# XT_short_bus_with_break-away_tab.net
KiCad netlist of a schematic drawn in Altium Designer
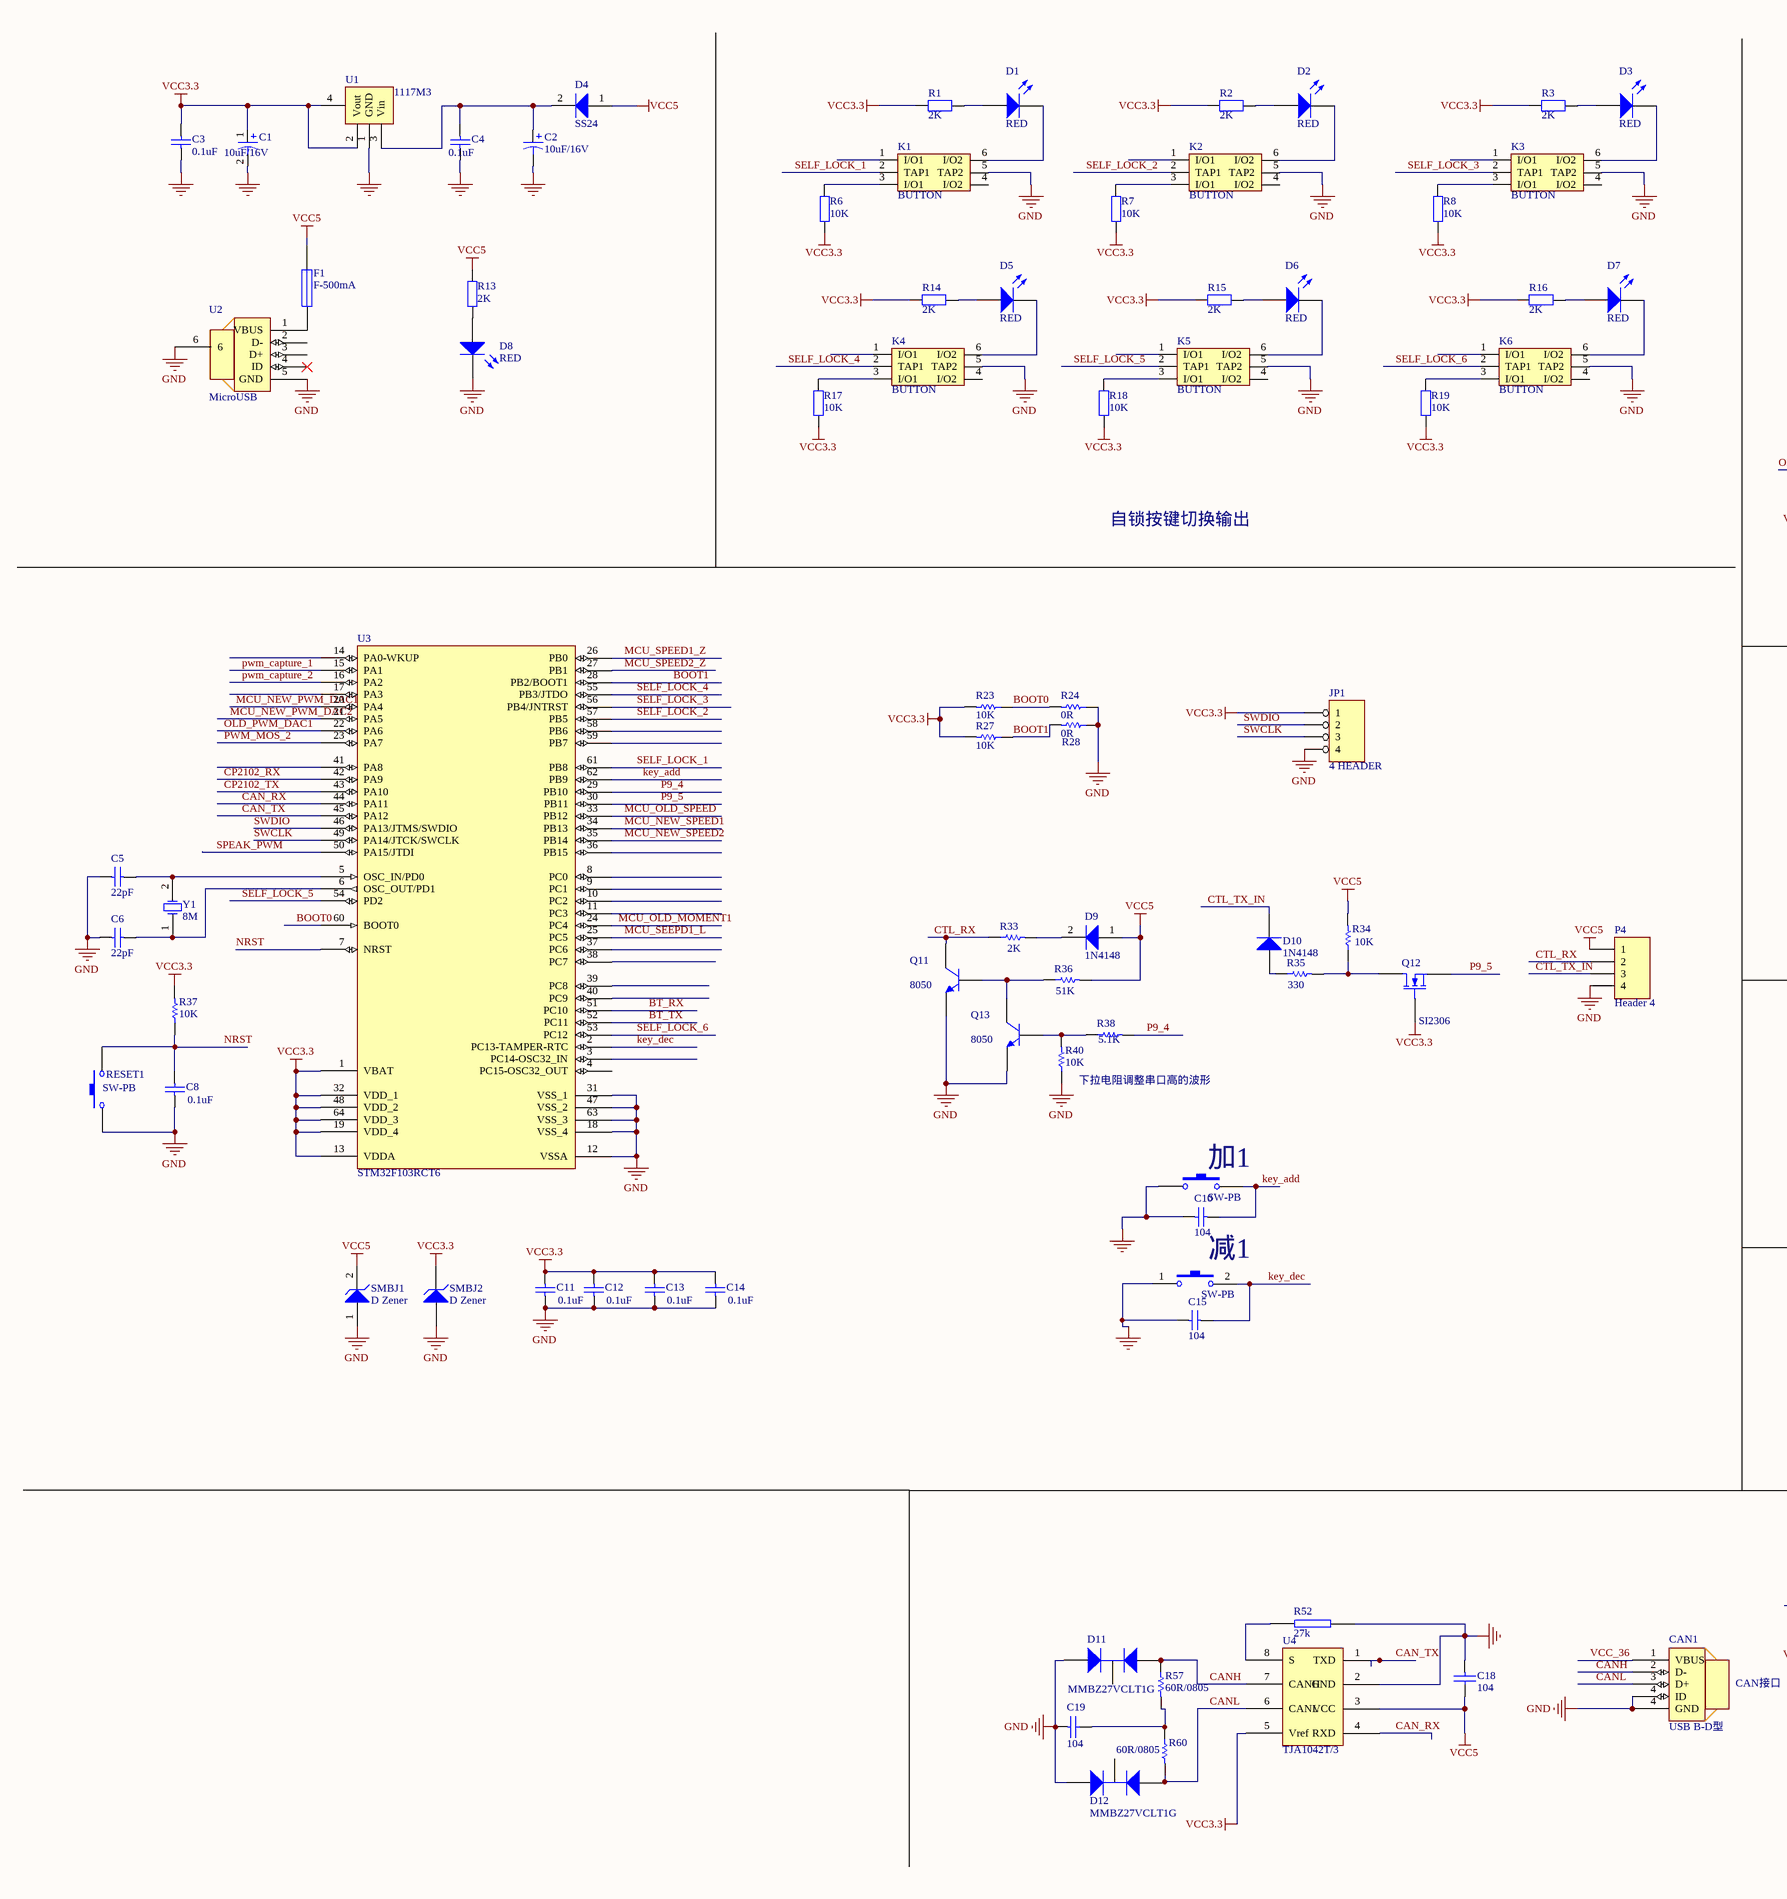
[diagram p0: XT short bus with break-away tab ( 5.2 X 4.2 inches).schdoc, left]
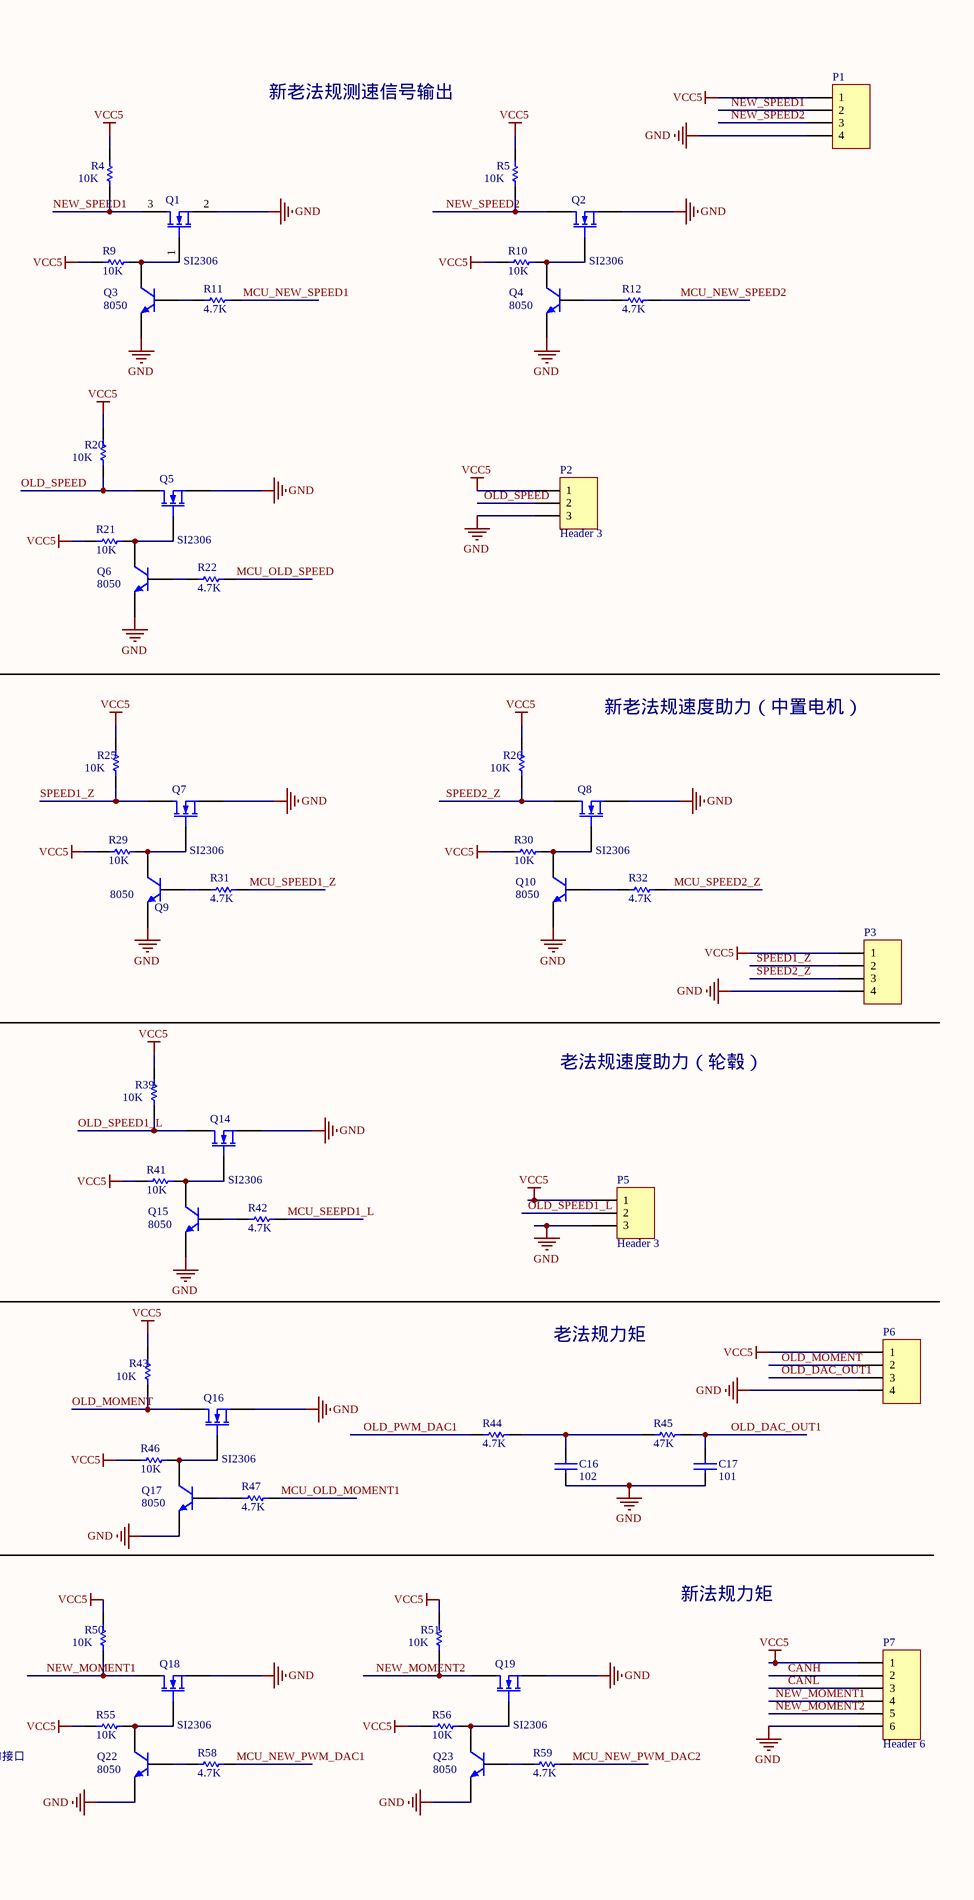
[diagram p1: XT short bus with break-away tab ( 5.2 X 4.2 inches).schdoc, right]

(export (version "E")
  (design (tool "Eeschema 10.0.6"))
  (components
    (comp (ref "C1")
      (value "10uF/16V")
      (footprint "1206")
      (description "Polarized Capacitor (Radial)")
      (fields (field (name "PUBLISHER") "Altium Limited"))
      (libsource (lib "") (part "Cap Pol1_1"))
    )
    (comp (ref "C2")
      (value "10uF/16V")
      (footprint "1206")
      (description "Polarized Capacitor (Radial)")
      (fields (field (name "PUBLISHER") "Altium Limited"))
      (libsource (lib "系统元件") (part "Cap Pol1"))
    )
    (comp (ref "C3")
      (value "0.1uF")
      (footprint "LC-0603_C")
      (description "Capacitor")
      (fields (field (name "PUBLISHER") "Altium Limited"))
      (libsource (lib "Miscellaneous Devices") (part "Cap"))
    )
    (comp (ref "C4")
      (value "0.1uF")
      (footprint "LC-0603_C")
      (description "Capacitor")
      (fields (field (name "PUBLISHER") "Altium Limited"))
      (libsource (lib "Miscellaneous Devices") (part "Cap"))
    )
    (comp (ref "C5")
      (value "22pF")
      (footprint "LC-0603_C")
      (description "Capacitor")
      (fields (field (name "PUBLISHER") "Altium Limited"))
      (libsource (lib "Miscellaneous Devices") (part "Cap"))
    )
    (comp (ref "C6")
      (value "22pF")
      (footprint "LC-0603_C")
      (description "Capacitor")
      (fields (field (name "PUBLISHER") "Altium Limited"))
      (libsource (lib "Miscellaneous Devices") (part "Cap"))
    )
    (comp (ref "C8")
      (value "0.1uF")
      (footprint "LC-0603_C")
      (description "Capacitor")
      (fields (field (name "PUBLISHER") "Altium Limited"))
      (libsource (lib "Miscellaneous Devices") (part "Cap"))
    )
    (comp (ref "C10")
      (value "104")
      (footprint "LC-0603_C")
      (description "Capacitor")
      (fields (field (name "PUBLISHER") "Altium Limited"))
      (libsource (lib "Miscellaneous Devices") (part "Cap"))
    )
    (comp (ref "C11")
      (value "0.1uF")
      (footprint "LC-0603_C")
      (description "Capacitor")
      (fields (field (name "PUBLISHER") "Altium Limited"))
      (libsource (lib "Miscellaneous Devices") (part "Cap"))
    )
    (comp (ref "C12")
      (value "0.1uF")
      (footprint "LC-0603_C")
      (description "Capacitor")
      (fields (field (name "PUBLISHER") "Altium Limited"))
      (libsource (lib "Miscellaneous Devices") (part "Cap"))
    )
    (comp (ref "C13")
      (value "0.1uF")
      (footprint "LC-0603_C")
      (description "Capacitor")
      (fields (field (name "PUBLISHER") "Altium Limited"))
      (libsource (lib "Miscellaneous Devices") (part "Cap"))
    )
    (comp (ref "C14")
      (value "0.1uF")
      (footprint "LC-0603_C")
      (description "Capacitor")
      (fields (field (name "PUBLISHER") "Altium Limited"))
      (libsource (lib "Miscellaneous Devices") (part "Cap"))
    )
    (comp (ref "C15")
      (value "104")
      (footprint "LC-0603_C")
      (description "Capacitor")
      (fields (field (name "PUBLISHER") "Altium Limited"))
      (libsource (lib "Miscellaneous Devices") (part "Cap"))
    )
    (comp (ref "C16")
      (value "102")
      (footprint "LC-0603_C")
      (description "Capacitor")
      (libsource (lib "*") (part "CAP"))
    )
    (comp (ref "C17")
      (value "101")
      (footprint "LC-0603_C")
      (description "Capacitor")
      (libsource (lib "*") (part "CAP"))
    )
    (comp (ref "C18")
      (value "104")
      (footprint "LC-0603_C")
      (description "Capacitor")
      (libsource (lib "*") (part "CAP"))
    )
    (comp (ref "C19")
      (value "104")
      (footprint "LC-0603_C")
      (description "Capacitor")
      (libsource (lib "*") (part "CAP"))
    )
    (comp (ref "CAN1")
      (value "USB B-D型")
      (footprint "USB B-D型_2")
      (description "MINIUSB")
      (libsource (lib "Hand_device") (part "MINIUSB"))
    )
    (comp (ref "D1")
      (value "RED")
      (footprint "LED_A2")
      (description "Typical INFRARED GaAs LED")
      (fields (field (name "PUBLISHER") "Altium Limited"))
      (libsource (lib "Miscellaneous Devices") (part "LED0"))
    )
    (comp (ref "D2")
      (value "RED")
      (footprint "LED_A2")
      (description "Typical INFRARED GaAs LED")
      (fields (field (name "PUBLISHER") "Altium Limited"))
      (libsource (lib "Miscellaneous Devices") (part "LED0"))
    )
    (comp (ref "D3")
      (value "RED")
      (footprint "LED_A2")
      (description "Typical INFRARED GaAs LED")
      (fields (field (name "PUBLISHER") "Altium Limited"))
      (libsource (lib "Miscellaneous Devices") (part "LED0"))
    )
    (comp (ref "D4")
      (value "SS24")
      (footprint "LC-SMA(DO-214AC)_S1")
      (description "1 Amp General Purpose Rectifier")
      (fields (field (name "PUBLISHER") "Altium Limited"))
      (libsource (lib "") (part "Diode 1N4007_1"))
    )
    (comp (ref "D5")
      (value "RED")
      (footprint "LED_A2")
      (description "Typical INFRARED GaAs LED")
      (fields (field (name "PUBLISHER") "Altium Limited"))
      (libsource (lib "Miscellaneous Devices") (part "LED0"))
    )
    (comp (ref "D6")
      (value "RED")
      (footprint "LED_A2")
      (description "Typical INFRARED GaAs LED")
      (fields (field (name "PUBLISHER") "Altium Limited"))
      (libsource (lib "Miscellaneous Devices") (part "LED0"))
    )
    (comp (ref "D7")
      (value "RED")
      (footprint "LED_A2")
      (description "Typical INFRARED GaAs LED")
      (fields (field (name "PUBLISHER") "Altium Limited"))
      (libsource (lib "Miscellaneous Devices") (part "LED0"))
    )
    (comp (ref "D8")
      (value "RED")
      (footprint "LED_A2")
      (description "Typical INFRARED GaAs LED")
      (fields (field (name "PUBLISHER") "Altium Limited"))
      (libsource (lib "Miscellaneous Devices") (part "LED0"))
    )
    (comp (ref "D9")
      (value "1N4148")
      (footprint "DIODE_SOP")
      (description "1 Amp General Purpose Rectifier")
      (fields (field (name "PUBLISHER") "Altium Limited"))
      (libsource (lib "") (part "Diode 1N4007_1"))
    )
    (comp (ref "D10")
      (value "1N4148")
      (footprint "DIODE_SOP")
      (description "1 Amp General Purpose Rectifier")
      (fields (field (name "PUBLISHER") "Altium Limited"))
      (libsource (lib "Miscellaneous Devices") (part "Diode 1N4007"))
    )
    (comp (ref "D11")
      (value "MMBZ27VCLT1G")
      (footprint "SOT-23")
      (description "TVS二极管,  MMBZ27VCLT1G, 27V, 两个共阴极, SOT-23")
      (libsource (lib "LEOPARD_SYSTEM") (part "BAT54C"))
    )
    (comp (ref "D12")
      (value "MMBZ27VCLT1G")
      (footprint "sot-23")
      (description "TVS二极管,  MMBZ27VCLT1G, 27V, 两个共阴极, SOT-23")
      (libsource (lib "LEOPARD_SYSTEM") (part "BAT54C"))
    )
    (comp (ref "F1")
      (value "F-500mA")
      (footprint "1206A")
      (description "FUSE1")
      (libsource (lib "Hand_device") (part "FUSE1"))
    )
    (comp (ref "JP1")
      (value "4 HEADER")
      (footprint "HDR1X4")
      (description "4 Pin Header")
      (libsource (lib "杂元件库") (part "4 HEADER"))
    )
    (comp (ref "K1")
      (value "BUTTON")
      (footprint "BTN8.5*8.5")
      (libsource (lib "MiniSTM32 V3.0封装库") (part "BUTTON"))
    )
    (comp (ref "K2")
      (value "BUTTON")
      (footprint "BTN8.5*8.5")
      (libsource (lib "MiniSTM32 V3.0封装库") (part "BUTTON"))
    )
    (comp (ref "K3")
      (value "BUTTON")
      (footprint "BTN8.5*8.5")
      (libsource (lib "MiniSTM32 V3.0封装库") (part "BUTTON"))
    )
    (comp (ref "K4")
      (value "BUTTON")
      (footprint "BTN8.5*8.5")
      (libsource (lib "MiniSTM32 V3.0封装库") (part "BUTTON"))
    )
    (comp (ref "K5")
      (value "BUTTON")
      (footprint "BTN8.5*8.5")
      (libsource (lib "MiniSTM32 V3.0封装库") (part "BUTTON"))
    )
    (comp (ref "K6")
      (value "BUTTON")
      (footprint "BTN8.5*8.5")
      (libsource (lib "MiniSTM32 V3.0封装库") (part "BUTTON"))
    )
    (comp (ref "P1")
      (value "Header 4")
      (footprint "HDR1X4")
      (description "Header, 4-Pin")
      (fields (field (name "PUBLISHER") "Altium Limited"))
      (libsource (lib "Miscellaneous Connectors") (part "Header 4"))
    )
    (comp (ref "P2")
      (value "Header 3")
      (footprint "HDR1X3")
      (description "Header, 3-Pin")
      (fields (field (name "PUBLISHER") "Altium Limited"))
      (libsource (lib "Miscellaneous Connectors") (part "Header 3"))
    )
    (comp (ref "P3")
      (value "Header 4")
      (footprint "HDR1X4")
      (description "Header, 4-Pin")
      (fields (field (name "PUBLISHER") "Altium Limited"))
      (libsource (lib "Miscellaneous Connectors") (part "Header 4"))
    )
    (comp (ref "P4")
      (value "Header 4")
      (footprint "HDR1X4")
      (description "Header, 4-Pin")
      (fields (field (name "PUBLISHER") "Altium Limited"))
      (libsource (lib "Miscellaneous Connectors") (part "Header 4"))
    )
    (comp (ref "P5")
      (value "Header 3")
      (footprint "HDR1X3")
      (description "Header, 3-Pin")
      (fields (field (name "PUBLISHER") "Altium Limited"))
      (libsource (lib "Miscellaneous Connectors") (part "Header 3"))
    )
    (comp (ref "P6")
      (value "Header 4")
      (footprint "HDR1X4")
      (description "Header, 4-Pin")
      (fields (field (name "PUBLISHER") "Altium Limited"))
      (libsource (lib "Miscellaneous Connectors") (part "Header 4"))
    )
    (comp (ref "P7")
      (value "Header 6")
      (footprint "HDR1X6")
      (description "Header, 6-Pin")
      (fields (field (name "PUBLISHER") "Altium Limited"))
      (libsource (lib "Miscellaneous Connectors") (part "Header 6"))
    )
    (comp (ref "Q1")
      (value "SI2306")
      (footprint "sot-23")
      (description "N-Channel MOSFET")
      (fields (field (name "PUBLISHER") "Altium Limited"))
      (libsource (lib "") (part "MOSFET-N_1"))
    )
    (comp (ref "Q2")
      (value "SI2306")
      (footprint "sot-23")
      (description "N-Channel MOSFET")
      (fields (field (name "PUBLISHER") "Altium Limited"))
      (libsource (lib "系统元件") (part "MOSFET-N"))
    )
    (comp (ref "Q3")
      (value "8050")
      (footprint "sot-23")
      (description "NPN General Purpose Amplifier")
      (fields (field (name "PUBLISHER") "Altium Limited"))
      (libsource (lib "系统元件") (part "2N3904"))
    )
    (comp (ref "Q4")
      (value "8050")
      (footprint "sot-23")
      (description "NPN General Purpose Amplifier")
      (fields (field (name "PUBLISHER") "Altium Limited"))
      (libsource (lib "系统元件") (part "2N3904"))
    )
    (comp (ref "Q5")
      (value "SI2306")
      (footprint "sot-23")
      (description "N-Channel MOSFET")
      (fields (field (name "PUBLISHER") "Altium Limited"))
      (libsource (lib "系统元件") (part "MOSFET-N"))
    )
    (comp (ref "Q6")
      (value "8050")
      (footprint "sot-23")
      (description "NPN General Purpose Amplifier")
      (fields (field (name "PUBLISHER") "Altium Limited"))
      (libsource (lib "系统元件") (part "2N3904"))
    )
    (comp (ref "Q7")
      (value "SI2306")
      (footprint "sot-23")
      (description "N-Channel MOSFET")
      (fields (field (name "PUBLISHER") "Altium Limited"))
      (libsource (lib "系统元件") (part "MOSFET-N"))
    )
    (comp (ref "Q8")
      (value "SI2306")
      (footprint "sot-23")
      (description "N-Channel MOSFET")
      (fields (field (name "PUBLISHER") "Altium Limited"))
      (libsource (lib "系统元件") (part "MOSFET-N"))
    )
    (comp (ref "Q9")
      (value "8050")
      (footprint "sot-23")
      (description "NPN General Purpose Amplifier")
      (fields (field (name "PUBLISHER") "Altium Limited"))
      (libsource (lib "系统元件") (part "2N3904"))
    )
    (comp (ref "Q10")
      (value "8050")
      (footprint "sot-23")
      (description "NPN General Purpose Amplifier")
      (fields (field (name "PUBLISHER") "Altium Limited"))
      (libsource (lib "系统元件") (part "2N3904"))
    )
    (comp (ref "Q11")
      (value "8050")
      (footprint "sot-23")
      (description "NPN General Purpose Amplifier")
      (fields (field (name "PUBLISHER") "Altium Limited"))
      (libsource (lib "系统元件") (part "2N3904"))
    )
    (comp (ref "Q12")
      (value "SI2306")
      (footprint "sot-23")
      (description "N-Channel MOSFET")
      (fields (field (name "PUBLISHER") "Altium Limited"))
      (libsource (lib "系统元件") (part "MOSFET-N"))
    )
    (comp (ref "Q13")
      (value "8050")
      (footprint "sot-23")
      (description "NPN General Purpose Amplifier")
      (fields (field (name "PUBLISHER") "Altium Limited"))
      (libsource (lib "系统元件") (part "2N3904"))
    )
    (comp (ref "Q14")
      (value "SI2306")
      (footprint "sot-23")
      (description "N-Channel MOSFET")
      (fields (field (name "PUBLISHER") "Altium Limited"))
      (libsource (lib "系统元件") (part "MOSFET-N"))
    )
    (comp (ref "Q15")
      (value "8050")
      (footprint "sot-23")
      (description "NPN General Purpose Amplifier")
      (fields (field (name "PUBLISHER") "Altium Limited"))
      (libsource (lib "系统元件") (part "2N3904"))
    )
    (comp (ref "Q16")
      (value "SI2306")
      (footprint "sot-23")
      (description "N-Channel MOSFET")
      (fields (field (name "PUBLISHER") "Altium Limited"))
      (libsource (lib "系统元件") (part "MOSFET-N"))
    )
    (comp (ref "Q17")
      (value "8050")
      (footprint "sot-23")
      (description "NPN General Purpose Amplifier")
      (fields (field (name "PUBLISHER") "Altium Limited"))
      (libsource (lib "系统元件") (part "2N3904"))
    )
    (comp (ref "Q18")
      (value "SI2306")
      (footprint "sot-23")
      (description "N-Channel MOSFET")
      (fields (field (name "PUBLISHER") "Altium Limited"))
      (libsource (lib "系统元件") (part "MOSFET-N"))
    )
    (comp (ref "Q19")
      (value "SI2306")
      (footprint "sot-23")
      (description "N-Channel MOSFET")
      (fields (field (name "PUBLISHER") "Altium Limited"))
      (libsource (lib "系统元件") (part "MOSFET-N"))
    )
    (comp (ref "Q22")
      (value "8050")
      (footprint "sot-23")
      (description "NPN General Purpose Amplifier")
      (fields (field (name "PUBLISHER") "Altium Limited"))
      (libsource (lib "系统元件") (part "2N3904"))
    )
    (comp (ref "Q23")
      (value "8050")
      (footprint "sot-23")
      (description "NPN General Purpose Amplifier")
      (fields (field (name "PUBLISHER") "Altium Limited"))
      (libsource (lib "系统元件") (part "2N3904"))
    )
    (comp (ref "R1")
      (value "2K")
      (footprint "LC-0603_R")
      (description "Resistor")
      (fields (field (name "PUBLISHER") "Altium Limited"))
      (libsource (lib "") (part "Res2_1"))
    )
    (comp (ref "R2")
      (value "2K")
      (footprint "LC-0603_R")
      (description "Resistor")
      (fields (field (name "PUBLISHER") "Altium Limited"))
      (libsource (lib "") (part "Res2_1"))
    )
    (comp (ref "R3")
      (value "2K")
      (footprint "LC-0603_R")
      (description "Resistor")
      (fields (field (name "PUBLISHER") "Altium Limited"))
      (libsource (lib "") (part "Res2_1"))
    )
    (comp (ref "R4")
      (value "10K")
      (footprint "LC-0603_R")
      (description "Resistor")
      (fields (field (name "PUBLISHER") "Altium Limited"))
      (libsource (lib "Miscellaneous Devices") (part "Res1"))
    )
    (comp (ref "R5")
      (value "10K")
      (footprint "LC-0603_R")
      (description "Resistor")
      (fields (field (name "PUBLISHER") "Altium Limited"))
      (libsource (lib "Miscellaneous Devices") (part "Res1"))
    )
    (comp (ref "R6")
      (value "10K")
      (footprint "LC-0603_R")
      (description "Resistor")
      (fields (field (name "PUBLISHER") "Altium Limited"))
      (libsource (lib "Miscellaneous Devices") (part "Res2"))
    )
    (comp (ref "R7")
      (value "10K")
      (footprint "LC-0603_R")
      (description "Resistor")
      (fields (field (name "PUBLISHER") "Altium Limited"))
      (libsource (lib "Miscellaneous Devices") (part "Res2"))
    )
    (comp (ref "R8")
      (value "10K")
      (footprint "LC-0603_R")
      (description "Resistor")
      (fields (field (name "PUBLISHER") "Altium Limited"))
      (libsource (lib "Miscellaneous Devices") (part "Res2"))
    )
    (comp (ref "R9")
      (value "10K")
      (footprint "LC-0603_R")
      (description "Resistor")
      (fields (field (name "PUBLISHER") "Altium Limited"))
      (libsource (lib "Miscellaneous Devices") (part "Res1"))
    )
    (comp (ref "R10")
      (value "10K")
      (footprint "LC-0603_R")
      (description "Resistor")
      (fields (field (name "PUBLISHER") "Altium Limited"))
      (libsource (lib "Miscellaneous Devices") (part "Res1"))
    )
    (comp (ref "R11")
      (value "4.7K")
      (footprint "LC-0603_R")
      (description "Resistor")
      (fields (field (name "PUBLISHER") "Altium Limited"))
      (libsource (lib "Miscellaneous Devices") (part "Res1"))
    )
    (comp (ref "R12")
      (value "4.7K")
      (footprint "LC-0603_R")
      (description "Resistor")
      (fields (field (name "PUBLISHER") "Altium Limited"))
      (libsource (lib "Miscellaneous Devices") (part "Res1"))
    )
    (comp (ref "R13")
      (value "2K")
      (footprint "LC-0603_R")
      (description "Resistor")
      (fields (field (name "PUBLISHER") "Altium Limited"))
      (libsource (lib "Miscellaneous Devices") (part "Res2"))
    )
    (comp (ref "R14")
      (value "2K")
      (footprint "LC-0603_R")
      (description "Resistor")
      (fields (field (name "PUBLISHER") "Altium Limited"))
      (libsource (lib "") (part "Res2_1"))
    )
    (comp (ref "R15")
      (value "2K")
      (footprint "LC-0603_R")
      (description "Resistor")
      (fields (field (name "PUBLISHER") "Altium Limited"))
      (libsource (lib "") (part "Res2_1"))
    )
    (comp (ref "R16")
      (value "2K")
      (footprint "LC-0603_R")
      (description "Resistor")
      (fields (field (name "PUBLISHER") "Altium Limited"))
      (libsource (lib "") (part "Res2_1"))
    )
    (comp (ref "R17")
      (value "10K")
      (footprint "LC-0603_R")
      (description "Resistor")
      (fields (field (name "PUBLISHER") "Altium Limited"))
      (libsource (lib "Miscellaneous Devices") (part "Res2"))
    )
    (comp (ref "R18")
      (value "10K")
      (footprint "LC-0603_R")
      (description "Resistor")
      (fields (field (name "PUBLISHER") "Altium Limited"))
      (libsource (lib "Miscellaneous Devices") (part "Res2"))
    )
    (comp (ref "R19")
      (value "10K")
      (footprint "LC-0603_R")
      (description "Resistor")
      (fields (field (name "PUBLISHER") "Altium Limited"))
      (libsource (lib "Miscellaneous Devices") (part "Res2"))
    )
    (comp (ref "R20")
      (value "10K")
      (footprint "LC-0603_R")
      (description "Resistor")
      (fields (field (name "PUBLISHER") "Altium Limited"))
      (libsource (lib "Miscellaneous Devices") (part "Res1"))
    )
    (comp (ref "R21")
      (value "10K")
      (footprint "LC-0603_R")
      (description "Resistor")
      (fields (field (name "PUBLISHER") "Altium Limited"))
      (libsource (lib "Miscellaneous Devices") (part "Res1"))
    )
    (comp (ref "R22")
      (value "4.7K")
      (footprint "LC-0603_R")
      (description "Resistor")
      (fields (field (name "PUBLISHER") "Altium Limited"))
      (libsource (lib "Miscellaneous Devices") (part "Res1"))
    )
    (comp (ref "R23")
      (value "10K")
      (footprint "LC-0603_R")
      (description "Resistor")
      (fields (field (name "PUBLISHER") "Altium Limited"))
      (libsource (lib "Miscellaneous Devices") (part "Res1"))
    )
    (comp (ref "R24")
      (value "0R")
      (footprint "LC-0603_R")
      (description "Resistor")
      (fields (field (name "PUBLISHER") "Altium Limited"))
      (libsource (lib "Miscellaneous Devices") (part "Res1"))
    )
    (comp (ref "R25")
      (value "10K")
      (footprint "LC-0603_R")
      (description "Resistor")
      (fields (field (name "PUBLISHER") "Altium Limited"))
      (libsource (lib "Miscellaneous Devices") (part "Res1"))
    )
    (comp (ref "R26")
      (value "10K")
      (footprint "LC-0603_R")
      (description "Resistor")
      (fields (field (name "PUBLISHER") "Altium Limited"))
      (libsource (lib "Miscellaneous Devices") (part "Res1"))
    )
    (comp (ref "R27")
      (value "10K")
      (footprint "LC-0603_R")
      (description "Resistor")
      (fields (field (name "PUBLISHER") "Altium Limited"))
      (libsource (lib "Miscellaneous Devices") (part "Res1"))
    )
    (comp (ref "R28")
      (value "0R")
      (footprint "LC-0603_R")
      (description "Resistor")
      (fields (field (name "PUBLISHER") "Altium Limited"))
      (libsource (lib "Miscellaneous Devices") (part "Res1"))
    )
    (comp (ref "R29")
      (value "10K")
      (footprint "LC-0603_R")
      (description "Resistor")
      (fields (field (name "PUBLISHER") "Altium Limited"))
      (libsource (lib "Miscellaneous Devices") (part "Res1"))
    )
    (comp (ref "R30")
      (value "10K")
      (footprint "LC-0603_R")
      (description "Resistor")
      (fields (field (name "PUBLISHER") "Altium Limited"))
      (libsource (lib "Miscellaneous Devices") (part "Res1"))
    )
    (comp (ref "R31")
      (value "4.7K")
      (footprint "LC-0603_R")
      (description "Resistor")
      (fields (field (name "PUBLISHER") "Altium Limited"))
      (libsource (lib "Miscellaneous Devices") (part "Res1"))
    )
    (comp (ref "R32")
      (value "4.7K")
      (footprint "LC-0603_R")
      (description "Resistor")
      (fields (field (name "PUBLISHER") "Altium Limited"))
      (libsource (lib "Miscellaneous Devices") (part "Res1"))
    )
    (comp (ref "R33")
      (value "2K")
      (footprint "LC-0603_R")
      (description "Resistor")
      (fields (field (name "PUBLISHER") "Altium Limited"))
      (libsource (lib "Miscellaneous Devices") (part "Res1"))
    )
    (comp (ref "R34")
      (value "10K")
      (footprint "LC-0603_R")
      (description "Resistor")
      (fields (field (name "PUBLISHER") "Altium Limited"))
      (libsource (lib "Miscellaneous Devices") (part "Res1"))
    )
    (comp (ref "R35")
      (value "330")
      (footprint "LC-0603_R")
      (description "Resistor")
      (fields (field (name "PUBLISHER") "Altium Limited"))
      (libsource (lib "Miscellaneous Devices") (part "Res1"))
    )
    (comp (ref "R36")
      (value "51K")
      (footprint "LC-0603_R")
      (description "Resistor")
      (fields (field (name "PUBLISHER") "Altium Limited"))
      (libsource (lib "Miscellaneous Devices") (part "Res1"))
    )
    (comp (ref "R37")
      (value "10K")
      (footprint "LC-0603_R")
      (description "Resistor")
      (fields (field (name "PUBLISHER") "Altium Limited"))
      (libsource (lib "Miscellaneous Devices") (part "Res1"))
    )
    (comp (ref "R38")
      (value "5.1K")
      (footprint "LC-0603_R")
      (description "Resistor")
      (fields (field (name "PUBLISHER") "Altium Limited"))
      (libsource (lib "Miscellaneous Devices") (part "Res1"))
    )
    (comp (ref "R39")
      (value "10K")
      (footprint "LC-0603_R")
      (description "Resistor")
      (fields (field (name "PUBLISHER") "Altium Limited"))
      (libsource (lib "Miscellaneous Devices") (part "Res1"))
    )
    (comp (ref "R40")
      (value "10K")
      (footprint "LC-0603_R")
      (description "Resistor")
      (fields (field (name "PUBLISHER") "Altium Limited"))
      (libsource (lib "Miscellaneous Devices") (part "Res1"))
    )
    (comp (ref "R41")
      (value "10K")
      (footprint "LC-0603_R")
      (description "Resistor")
      (fields (field (name "PUBLISHER") "Altium Limited"))
      (libsource (lib "Miscellaneous Devices") (part "Res1"))
    )
    (comp (ref "R42")
      (value "4.7K")
      (footprint "LC-0603_R")
      (description "Resistor")
      (fields (field (name "PUBLISHER") "Altium Limited"))
      (libsource (lib "Miscellaneous Devices") (part "Res1"))
    )
    (comp (ref "R43")
      (value "10K")
      (footprint "LC-0603_R")
      (description "Resistor")
      (fields (field (name "PUBLISHER") "Altium Limited"))
      (libsource (lib "Miscellaneous Devices") (part "Res1"))
    )
    (comp (ref "R44")
      (value "4.7K")
      (footprint "LC-0603_R")
      (description "Resistor")
      (fields (field (name "PUBLISHER") "Altium Limited"))
      (libsource (lib "Miscellaneous Devices") (part "Res1"))
    )
    (comp (ref "R45")
      (value "47K")
      (footprint "LC-0603_R")
      (description "Resistor")
      (fields (field (name "PUBLISHER") "Altium Limited"))
      (libsource (lib "Miscellaneous Devices") (part "Res1"))
    )
    (comp (ref "R46")
      (value "10K")
      (footprint "LC-0603_R")
      (description "Resistor")
      (fields (field (name "PUBLISHER") "Altium Limited"))
      (libsource (lib "Miscellaneous Devices") (part "Res1"))
    )
    (comp (ref "R47")
      (value "4.7K")
      (footprint "LC-0603_R")
      (description "Resistor")
      (fields (field (name "PUBLISHER") "Altium Limited"))
      (libsource (lib "Miscellaneous Devices") (part "Res1"))
    )
    (comp (ref "R50")
      (value "10K")
      (footprint "LC-0603_R")
      (description "Resistor")
      (fields (field (name "PUBLISHER") "Altium Limited"))
      (libsource (lib "Miscellaneous Devices") (part "Res1"))
    )
    (comp (ref "R51")
      (value "10K")
      (footprint "LC-0603_R")
      (description "Resistor")
      (fields (field (name "PUBLISHER") "Altium Limited"))
      (libsource (lib "Miscellaneous Devices") (part "Res1"))
    )
    (comp (ref "R52") (value "27k") (footprint "LC-0603_R") (libsource (lib "*") (part "RES2")))
    (comp (ref "R55")
      (value "10K")
      (footprint "LC-0603_R")
      (description "Resistor")
      (fields (field (name "PUBLISHER") "Altium Limited"))
      (libsource (lib "Miscellaneous Devices") (part "Res1"))
    )
    (comp (ref "R56")
      (value "10K")
      (footprint "LC-0603_R")
      (description "Resistor")
      (fields (field (name "PUBLISHER") "Altium Limited"))
      (libsource (lib "Miscellaneous Devices") (part "Res1"))
    )
    (comp (ref "R57")
      (value "60R/0805")
      (footprint "LC-0603_R")
      (description "Resistor")
      (fields (field (name "PUBLISHER") "Altium Limited"))
      (libsource (lib "Miscellaneous Devices") (part "Res1"))
    )
    (comp (ref "R58")
      (value "4.7K")
      (footprint "LC-0603_R")
      (description "Resistor")
      (fields (field (name "PUBLISHER") "Altium Limited"))
      (libsource (lib "Miscellaneous Devices") (part "Res1"))
    )
    (comp (ref "R59")
      (value "4.7K")
      (footprint "LC-0603_R")
      (description "Resistor")
      (fields (field (name "PUBLISHER") "Altium Limited"))
      (libsource (lib "Miscellaneous Devices") (part "Res1"))
    )
    (comp (ref "R60")
      (value "60R/0805")
      (footprint "LC-0603_R")
      (description "Resistor")
      (fields (field (name "PUBLISHER") "Altium Limited"))
      (libsource (lib "Miscellaneous Devices") (part "Res1"))
    )
    (comp (ref "RESET1")
      (value "SW-PB")
      (footprint "按键-贴片-6X6")
      (description "Switch")
      (fields (field (name "PUBLISHER") "Altium Limited"))
      (libsource (lib "Miscellaneous Devices") (part "SW-PB"))
    )
    (comp (ref "SMBJ1")
      (value "D Zener")
      (footprint "LC-SMB(DO-214AA)_S1")
      (description "Zener Diode")
      (fields (field (name "PUBLISHER") "Altium Limited"))
      (libsource (lib "") (part "D Zener_1"))
    )
    (comp (ref "SMBJ2")
      (value "D Zener")
      (footprint "LC-SMB(DO-214AA)_S1")
      (description "Zener Diode")
      (fields (field (name "PUBLISHER") "Altium Limited"))
      (libsource (lib "Miscellaneous Devices") (part "D Zener"))
    )
    (comp (ref "U1") (value "1117M3") (footprint "SOT-223") (libsource (lib "Schlib") (part "1117M3")))
    (comp (ref "U2")
      (value "MicroUSB")
      (footprint "USB1_mini_直插")
      (description "MINIUSB")
      (libsource (lib "") (part "MINIUSB_1"))
    )
    (comp (ref "U3")
      (value "STM32F103RCT6")
      (footprint "LC-LQFP-64_10X10X05P")
      (description "STM32 ARM-based 32-bit MCU with 128 Kbytes Flash, 64-pin LQFP, Industrial Temperature")
      (fields (field (name "PUBLISHER") "Altium Limited"))
      (libsource (lib "ST Microcontroller 32-Bit STM32") (part "STM32F103RBT6"))
    )
    (comp (ref "U4")
      (value "TJA1042T/3")
      (footprint "LC-SOP-8_150mil")
      (libsource (lib "*") (part "TJA1050"))
    )
    (comp (ref "Y1")
      (value "8M")
      (footprint "XTAL_US")
      (description "Crystal Oscillator")
      (fields (field (name "PUBLISHER") "Altium Limited"))
      (libsource (lib "Miscellaneous Devices") (part "XTAL"))
    )
    (comp (ref "减1")
      (value "SW-PB")
      (footprint "按键-贴片-6X6")
      (description "Switch")
      (fields (field (name "PUBLISHER") "Altium Limited"))
      (libsource (lib "") (part "SW-PB_1"))
    )
    (comp (ref "加1")
      (value "SW-PB")
      (footprint "按键-贴片-6X6")
      (description "Switch")
      (fields (field (name "PUBLISHER") "Altium Limited"))
      (libsource (lib "Miscellaneous Devices") (part "SW-PB"))
    )
  )
  (nets
    (net (code "1") (name "/BOOT0") (class "Default")
      (node (ref "R23") (pin "1") (pinfunction "1_1") (pintype "passive"))
      (node (ref "R24") (pin "2") (pinfunction "2_2") (pintype "passive"))
      (node (ref "U3") (pin "60") (pinfunction "BOOT0_60") (pintype "input"))
    )
    (net (code "2") (name "/BOOT1") (class "Default")
      (node (ref "R27") (pin "1") (pinfunction "1_1") (pintype "passive"))
      (node (ref "R28") (pin "2") (pinfunction "2_2") (pintype "passive"))
      (node (ref "U3") (pin "28") (pinfunction "PB2/BOOT1_28") (pintype "bidirectional"))
    )
    (net (code "3") (name "/BT_RX") (class "Default")
      (node (ref "U3") (pin "51") (pinfunction "PC10_51") (pintype "bidirectional"))
    )
    (net (code "4") (name "/BT_TX") (class "Default")
      (node (ref "U3") (pin "52") (pinfunction "PC11_52") (pintype "bidirectional"))
    )
    (net (code "5") (name "/CANH") (class "Default")
      (node (ref "CAN1") (pin "2") (pinfunction "D-_2") (pintype "bidirectional"))
      (node (ref "D11") (pin "2") (pinfunction "C_2") (pintype "passive"))
      (node (ref "P7") (pin "2") (pinfunction "2_2") (pintype "passive"))
      (node (ref "R57") (pin "1") (pinfunction "1_1") (pintype "passive"))
      (node (ref "U4") (pin "7") (pinfunction "CANH_7") (pintype "passive"))
    )
    (net (code "6") (name "/CANL") (class "Default")
      (node (ref "CAN1") (pin "3") (pinfunction "D+_3") (pintype "bidirectional"))
      (node (ref "D12") (pin "1") (pinfunction "A_1") (pintype "passive"))
      (node (ref "P7") (pin "3") (pinfunction "3_3") (pintype "passive"))
      (node (ref "R60") (pin "2") (pinfunction "2_2") (pintype "passive"))
      (node (ref "U4") (pin "6") (pinfunction "CANL_6") (pintype "passive"))
    )
    (net (code "7") (name "/CAN_RX") (class "Default")
      (node (ref "U3") (pin "44") (pinfunction "PA11_44") (pintype "bidirectional"))
      (node (ref "U4") (pin "4") (pinfunction "RXD_4") (pintype "passive"))
    )
    (net (code "8") (name "/CAN_TX") (class "Default")
      (node (ref "U3") (pin "45") (pinfunction "PA12_45") (pintype "bidirectional"))
      (node (ref "U4") (pin "1") (pinfunction "TXD_1") (pintype "passive"))
    )
    (net (code "9") (name "/CP2102_RX") (class "Default")
      (node (ref "U3") (pin "42") (pinfunction "PA9_42") (pintype "bidirectional"))
    )
    (net (code "10") (name "/CP2102_TX") (class "Default")
      (node (ref "U3") (pin "43") (pinfunction "PA10_43") (pintype "bidirectional"))
    )
    (net (code "11") (name "/CTL_RX") (class "Default")
      (node (ref "P4") (pin "2") (pinfunction "2_2") (pintype "passive"))
      (node (ref "Q11") (pin "3") (pinfunction "C_3") (pintype "passive"))
      (node (ref "R33") (pin "1") (pinfunction "1_1") (pintype "passive"))
    )
    (net (code "12") (name "/CTL_TX_IN") (class "Default")
      (node (ref "D10") (pin "2") (pinfunction "K_2") (pintype "passive"))
      (node (ref "P4") (pin "3") (pinfunction "3_3") (pintype "passive"))
    )
    (net (code "13") (name "/MCU_NEW_PWM_DAC1") (class "Default")
      (node (ref "R58") (pin "1") (pinfunction "1_1") (pintype "passive"))
      (node (ref "U3") (pin "20") (pinfunction "PA4_20") (pintype "bidirectional"))
    )
    (net (code "14") (name "/MCU_NEW_PWM_DAC2") (class "Default")
      (node (ref "R59") (pin "1") (pinfunction "1_1") (pintype "passive"))
      (node (ref "U3") (pin "21") (pinfunction "PA5_21") (pintype "bidirectional"))
    )
    (net (code "15") (name "/MCU_NEW_SPEED1") (class "Default")
      (node (ref "R11") (pin "1") (pinfunction "1_1") (pintype "passive"))
      (node (ref "U3") (pin "34") (pinfunction "PB13_34") (pintype "bidirectional"))
    )
    (net (code "16") (name "/MCU_NEW_SPEED2") (class "Default")
      (node (ref "R12") (pin "1") (pinfunction "1_1") (pintype "passive"))
      (node (ref "U3") (pin "35") (pinfunction "PB14_35") (pintype "bidirectional"))
    )
    (net (code "17") (name "/MCU_OLD_MOMENT1") (class "Default")
      (node (ref "R47") (pin "1") (pinfunction "1_1") (pintype "passive"))
      (node (ref "U3") (pin "24") (pinfunction "PC4_24") (pintype "bidirectional"))
    )
    (net (code "18") (name "/MCU_OLD_SPEED") (class "Default")
      (node (ref "R22") (pin "1") (pinfunction "1_1") (pintype "passive"))
      (node (ref "U3") (pin "33") (pinfunction "PB12_33") (pintype "bidirectional"))
    )
    (net (code "19") (name "/MCU_SEEPD1_L") (class "Default")
      (node (ref "R42") (pin "1") (pinfunction "1_1") (pintype "passive"))
      (node (ref "U3") (pin "25") (pinfunction "PC5_25") (pintype "bidirectional"))
    )
    (net (code "20") (name "/MCU_SPEED1_Z") (class "Default")
      (node (ref "R31") (pin "1") (pinfunction "1_1") (pintype "passive"))
      (node (ref "U3") (pin "26") (pinfunction "PB0_26") (pintype "bidirectional"))
    )
    (net (code "21") (name "/MCU_SPEED2_Z") (class "Default")
      (node (ref "R32") (pin "1") (pinfunction "1_1") (pintype "passive"))
      (node (ref "U3") (pin "27") (pinfunction "PB1_27") (pintype "bidirectional"))
    )
    (net (code "22") (name "/NEW_MOMENT1") (class "Default")
      (node (ref "P7") (pin "4") (pinfunction "4_4") (pintype "passive"))
      (node (ref "Q18") (pin "3") (pinfunction "D_3") (pintype "passive"))
      (node (ref "R50") (pin "1") (pinfunction "1_1") (pintype "passive"))
    )
    (net (code "23") (name "/NEW_MOMENT2") (class "Default")
      (node (ref "P7") (pin "5") (pinfunction "5_5") (pintype "passive"))
      (node (ref "Q19") (pin "3") (pinfunction "D_3") (pintype "passive"))
      (node (ref "R51") (pin "1") (pinfunction "1_1") (pintype "passive"))
    )
    (net (code "24") (name "/NEW_SPEED1") (class "Default")
      (node (ref "P1") (pin "2") (pinfunction "2_2") (pintype "passive"))
      (node (ref "Q1") (pin "3") (pinfunction "D_3") (pintype "passive"))
      (node (ref "R4") (pin "1") (pinfunction "1_1") (pintype "passive"))
    )
    (net (code "25") (name "/NEW_SPEED2") (class "Default")
      (node (ref "P1") (pin "3") (pinfunction "3_3") (pintype "passive"))
      (node (ref "Q2") (pin "3") (pinfunction "D_3") (pintype "passive"))
      (node (ref "R5") (pin "1") (pinfunction "1_1") (pintype "passive"))
    )
    (net (code "26") (name "/NRST") (class "Default")
      (node (ref "C8") (pin "2") (pinfunction "2_2") (pintype "passive"))
      (node (ref "R37") (pin "1") (pinfunction "1_1") (pintype "passive"))
      (node (ref "RESET1") (pin "2") (pinfunction "2_2") (pintype "passive"))
      (node (ref "U3") (pin "7") (pinfunction "NRST_7") (pintype "bidirectional"))
    )
    (net (code "27") (name "/OLD_DAC_OUT1") (class "Default")
      (node (ref "C17") (pin "2") (pinfunction "2_2") (pintype "passive"))
      (node (ref "P6") (pin "3") (pinfunction "3_3") (pintype "passive"))
      (node (ref "R45") (pin "1") (pinfunction "1_1") (pintype "passive"))
    )
    (net (code "28") (name "/OLD_MOMENT") (class "Default")
      (node (ref "P6") (pin "2") (pinfunction "2_2") (pintype "passive"))
      (node (ref "Q16") (pin "3") (pinfunction "D_3") (pintype "passive"))
      (node (ref "R43") (pin "1") (pinfunction "1_1") (pintype "passive"))
    )
    (net (code "29") (name "/OLD_PWM_DAC1") (class "Default")
      (node (ref "R44") (pin "2") (pinfunction "2_2") (pintype "passive"))
      (node (ref "U3") (pin "22") (pinfunction "PA6_22") (pintype "bidirectional"))
    )
    (net (code "30") (name "/OLD_SPEED") (class "Default")
      (node (ref "P2") (pin "2") (pinfunction "2_2") (pintype "passive"))
      (node (ref "Q5") (pin "3") (pinfunction "D_3") (pintype "passive"))
      (node (ref "R20") (pin "1") (pinfunction "1_1") (pintype "passive"))
    )
    (net (code "31") (name "/OLD_SPEED1_L") (class "Default")
      (node (ref "P5") (pin "2") (pinfunction "2_2") (pintype "passive"))
      (node (ref "Q14") (pin "3") (pinfunction "D_3") (pintype "passive"))
      (node (ref "R39") (pin "1") (pinfunction "1_1") (pintype "passive"))
    )
    (net (code "32") (name "/P9_4") (class "Default")
      (node (ref "R38") (pin "2") (pinfunction "2_2") (pintype "passive"))
      (node (ref "U3") (pin "29") (pinfunction "PB10_29") (pintype "bidirectional"))
    )
    (net (code "33") (name "/P9_5") (class "Default")
      (node (ref "Q12") (pin "2") (pinfunction "S_2") (pintype "passive"))
      (node (ref "U3") (pin "30") (pinfunction "PB11_30") (pintype "bidirectional"))
    )
    (net (code "34") (name "/PWM_MOS_2") (class "Default")
      (node (ref "U3") (pin "23") (pinfunction "PA7_23") (pintype "bidirectional"))
    )
    (net (code "35") (name "/SELF_LOCK_1") (class "Default")
      (node (ref "K1") (pin "2") (pinfunction "TAP1_2") (pintype "passive"))
      (node (ref "U3") (pin "61") (pinfunction "PB8_61") (pintype "bidirectional"))
    )
    (net (code "36") (name "/SELF_LOCK_2") (class "Default")
      (node (ref "K2") (pin "2") (pinfunction "TAP1_2") (pintype "passive"))
      (node (ref "U3") (pin "57") (pinfunction "PB5_57") (pintype "bidirectional"))
    )
    (net (code "37") (name "/SELF_LOCK_3") (class "Default")
      (node (ref "K3") (pin "2") (pinfunction "TAP1_2") (pintype "passive"))
      (node (ref "U3") (pin "56") (pinfunction "PB4/JNTRST_56") (pintype "bidirectional"))
    )
    (net (code "38") (name "/SELF_LOCK_4") (class "Default")
      (node (ref "K4") (pin "2") (pinfunction "TAP1_2") (pintype "passive"))
      (node (ref "U3") (pin "55") (pinfunction "PB3/JTDO_55") (pintype "bidirectional"))
    )
    (net (code "39") (name "/SELF_LOCK_5") (class "Default")
      (node (ref "K5") (pin "2") (pinfunction "TAP1_2") (pintype "passive"))
      (node (ref "U3") (pin "54") (pinfunction "PD2_54") (pintype "bidirectional"))
    )
    (net (code "40") (name "/SELF_LOCK_6") (class "Default")
      (node (ref "K6") (pin "2") (pinfunction "TAP1_2") (pintype "passive"))
      (node (ref "U3") (pin "53") (pinfunction "PC12_53") (pintype "bidirectional"))
    )
    (net (code "41") (name "/SPEAK_PWM") (class "Default")
      (node (ref "U3") (pin "50") (pinfunction "PA15/JTDI_50") (pintype "bidirectional"))
    )
    (net (code "42") (name "/SPEED1_Z") (class "Default")
      (node (ref "P3") (pin "2") (pinfunction "2_2") (pintype "passive"))
      (node (ref "Q7") (pin "3") (pinfunction "D_3") (pintype "passive"))
      (node (ref "R25") (pin "1") (pinfunction "1_1") (pintype "passive"))
    )
    (net (code "43") (name "/SPEED2_Z") (class "Default")
      (node (ref "P3") (pin "3") (pinfunction "3_3") (pintype "passive"))
      (node (ref "Q8") (pin "3") (pinfunction "D_3") (pintype "passive"))
      (node (ref "R26") (pin "1") (pinfunction "1_1") (pintype "passive"))
    )
    (net (code "44") (name "/SWCLK") (class "Default")
      (node (ref "JP1") (pin "3") (pinfunction "3_3") (pintype "passive"))
      (node (ref "U3") (pin "49") (pinfunction "PA14/JTCK/SWCLK_49") (pintype "bidirectional"))
    )
    (net (code "45") (name "/SWDIO") (class "Default")
      (node (ref "JP1") (pin "2") (pinfunction "2_2") (pintype "passive"))
      (node (ref "U3") (pin "46") (pinfunction "PA13/JTMS/SWDIO_46") (pintype "bidirectional"))
    )
    (net (code "46") (name "/VCC_36") (class "Default")
      (node (ref "CAN1") (pin "1") (pinfunction "VBUS_1") (pintype "power_in"))
    )
    (net (code "47") (name "/key_add") (class "Default")
      (node (ref "C10") (pin "2") (pinfunction "2_2") (pintype "passive"))
      (node (ref "U3") (pin "62") (pinfunction "PB9_62") (pintype "bidirectional"))
      (node (ref "加1") (pin "2") (pinfunction "2_2") (pintype "passive"))
    )
    (net (code "48") (name "/key_dec") (class "Default")
      (node (ref "C15") (pin "2") (pinfunction "2_2") (pintype "passive"))
      (node (ref "U3") (pin "2") (pinfunction "PC13-TAMPER-RTC_2") (pintype "bidirectional"))
      (node (ref "减1") (pin "2") (pinfunction "2_2") (pintype "passive"))
    )
    (net (code "49") (name "/pwm_capture_1") (class "Default")
      (node (ref "U3") (pin "15") (pinfunction "PA1_15") (pintype "bidirectional"))
    )
    (net (code "50") (name "/pwm_capture_2") (class "Default")
      (node (ref "U3") (pin "16") (pinfunction "PA2_16") (pintype "bidirectional"))
    )
    (net (code "51") (name "GND") (class "Default")
      (node (ref "C1") (pin "2") (pinfunction "2_2") (pintype "passive"))
      (node (ref "C10") (pin "1") (pinfunction "1_1") (pintype "passive"))
      (node (ref "C11") (pin "1") (pinfunction "1_1") (pintype "passive"))
      (node (ref "C12") (pin "1") (pinfunction "1_1") (pintype "passive"))
      (node (ref "C13") (pin "1") (pinfunction "1_1") (pintype "passive"))
      (node (ref "C14") (pin "1") (pinfunction "1_1") (pintype "passive"))
      (node (ref "C15") (pin "1") (pinfunction "1_1") (pintype "passive"))
      (node (ref "C16") (pin "1") (pinfunction "1_1") (pintype "passive"))
      (node (ref "C17") (pin "1") (pinfunction "1_1") (pintype "passive"))
      (node (ref "C18") (pin "1") (pinfunction "1_1") (pintype "passive"))
      (node (ref "C19") (pin "1") (pinfunction "1_1") (pintype "passive"))
      (node (ref "C2") (pin "2") (pinfunction "2_2") (pintype "passive"))
      (node (ref "C3") (pin "2") (pinfunction "2_2") (pintype "passive"))
      (node (ref "C4") (pin "2") (pinfunction "2_2") (pintype "passive"))
      (node (ref "C5") (pin "1") (pinfunction "1_1") (pintype "passive"))
      (node (ref "C6") (pin "1") (pinfunction "1_1") (pintype "passive"))
      (node (ref "C8") (pin "1") (pinfunction "1_1") (pintype "passive"))
      (node (ref "CAN1") (pin "4") (pinfunction "GND_4") (pintype "power_in"))
      (node (ref "D11") (pin "1") (pinfunction "A_1") (pintype "passive"))
      (node (ref "D12") (pin "2") (pinfunction "C_2") (pintype "passive"))
      (node (ref "D8") (pin "2") (pinfunction "K_2") (pintype "passive"))
      (node (ref "JP1") (pin "4") (pinfunction "4_4") (pintype "passive"))
      (node (ref "K1") (pin "5") (pinfunction "TAP2_5") (pintype "passive"))
      (node (ref "K2") (pin "5") (pinfunction "TAP2_5") (pintype "passive"))
      (node (ref "K3") (pin "5") (pinfunction "TAP2_5") (pintype "passive"))
      (node (ref "K4") (pin "5") (pinfunction "TAP2_5") (pintype "passive"))
      (node (ref "K5") (pin "5") (pinfunction "TAP2_5") (pintype "passive"))
      (node (ref "K6") (pin "5") (pinfunction "TAP2_5") (pintype "passive"))
      (node (ref "P1") (pin "4") (pinfunction "4_4") (pintype "passive"))
      (node (ref "P2") (pin "3") (pinfunction "3_3") (pintype "passive"))
      (node (ref "P3") (pin "4") (pinfunction "4_4") (pintype "passive"))
      (node (ref "P4") (pin "4") (pinfunction "4_4") (pintype "passive"))
      (node (ref "P5") (pin "3") (pinfunction "3_3") (pintype "passive"))
      (node (ref "P6") (pin "4") (pinfunction "4_4") (pintype "passive"))
      (node (ref "P7") (pin "6") (pinfunction "6_6") (pintype "passive"))
      (node (ref "Q1") (pin "2") (pinfunction "S_2") (pintype "passive"))
      (node (ref "Q10") (pin "2") (pinfunction "E_2") (pintype "passive"))
      (node (ref "Q11") (pin "2") (pinfunction "E_2") (pintype "passive"))
      (node (ref "Q13") (pin "2") (pinfunction "E_2") (pintype "passive"))
      (node (ref "Q14") (pin "2") (pinfunction "S_2") (pintype "passive"))
      (node (ref "Q15") (pin "2") (pinfunction "E_2") (pintype "passive"))
      (node (ref "Q16") (pin "2") (pinfunction "S_2") (pintype "passive"))
      (node (ref "Q17") (pin "2") (pinfunction "E_2") (pintype "passive"))
      (node (ref "Q18") (pin "2") (pinfunction "S_2") (pintype "passive"))
      (node (ref "Q19") (pin "2") (pinfunction "S_2") (pintype "passive"))
      (node (ref "Q2") (pin "2") (pinfunction "S_2") (pintype "passive"))
      (node (ref "Q22") (pin "2") (pinfunction "E_2") (pintype "passive"))
      (node (ref "Q23") (pin "2") (pinfunction "E_2") (pintype "passive"))
      (node (ref "Q3") (pin "2") (pinfunction "E_2") (pintype "passive"))
      (node (ref "Q4") (pin "2") (pinfunction "E_2") (pintype "passive"))
      (node (ref "Q5") (pin "2") (pinfunction "S_2") (pintype "passive"))
      (node (ref "Q6") (pin "2") (pinfunction "E_2") (pintype "passive"))
      (node (ref "Q7") (pin "2") (pinfunction "S_2") (pintype "passive"))
      (node (ref "Q8") (pin "2") (pinfunction "S_2") (pintype "passive"))
      (node (ref "Q9") (pin "2") (pinfunction "E_2") (pintype "passive"))
      (node (ref "R24") (pin "1") (pinfunction "1_1") (pintype "passive"))
      (node (ref "R28") (pin "1") (pinfunction "1_1") (pintype "passive"))
      (node (ref "R40") (pin "1") (pinfunction "1_1") (pintype "passive"))
      (node (ref "R52") (pin "1") (pinfunction "1_1") (pintype "passive"))
      (node (ref "RESET1") (pin "1") (pinfunction "1_1") (pintype "passive"))
      (node (ref "SMBJ1") (pin "1") (pinfunction "A_1") (pintype "passive"))
      (node (ref "SMBJ2") (pin "1") (pinfunction "A_1") (pintype "passive"))
      (node (ref "U1") (pin "1") (pinfunction "GND_1") (pintype "passive"))
      (node (ref "U2") (pin "5") (pinfunction "GND_5") (pintype "power_in"))
      (node (ref "U2") (pin "6") (pinfunction "6_6") (pintype "passive"))
      (node (ref "U3") (pin "12") (pinfunction "VSSA_12") (pintype "power_in"))
      (node (ref "U3") (pin "18") (pinfunction "VSS_4_18") (pintype "power_in"))
      (node (ref "U3") (pin "31") (pinfunction "VSS_1_31") (pintype "power_in"))
      (node (ref "U3") (pin "47") (pinfunction "VSS_2_47") (pintype "power_in"))
      (node (ref "U3") (pin "63") (pinfunction "VSS_3_63") (pintype "power_in"))
      (node (ref "U4") (pin "2") (pinfunction "GND_2") (pintype "passive"))
      (node (ref "减1") (pin "1") (pinfunction "1_1") (pintype "passive"))
      (node (ref "加1") (pin "1") (pinfunction "1_1") (pintype "passive"))
    )
    (net (code "52") (name "Net-(C16-Pad2)") (class "Default")
      (node (ref "C16") (pin "2") (pinfunction "2_2") (pintype "passive"))
      (node (ref "R44") (pin "1") (pinfunction "1_1") (pintype "passive"))
      (node (ref "R45") (pin "2") (pinfunction "2_2") (pintype "passive"))
    )
    (net (code "53") (name "Net-(C19-Pad2)") (class "Default")
      (node (ref "C19") (pin "2") (pinfunction "2_2") (pintype "passive"))
      (node (ref "R57") (pin "2") (pinfunction "2_2") (pintype "passive"))
      (node (ref "R60") (pin "1") (pinfunction "1_1") (pintype "passive"))
    )
    (net (code "54") (name "Net-(D1-A)") (class "Default")
      (node (ref "D1") (pin "1") (pinfunction "A_1") (pintype "passive"))
      (node (ref "R1") (pin "1") (pinfunction "1_1") (pintype "passive"))
    )
    (net (code "55") (name "Net-(D1-K)") (class "Default")
      (node (ref "D1") (pin "2") (pinfunction "K_2") (pintype "passive"))
      (node (ref "K1") (pin "6") (pinfunction "I/O2_6") (pintype "passive"))
    )
    (net (code "56") (name "Net-(D2-A)") (class "Default")
      (node (ref "D2") (pin "1") (pinfunction "A_1") (pintype "passive"))
      (node (ref "R2") (pin "1") (pinfunction "1_1") (pintype "passive"))
    )
    (net (code "57") (name "Net-(D2-K)") (class "Default")
      (node (ref "D2") (pin "2") (pinfunction "K_2") (pintype "passive"))
      (node (ref "K2") (pin "6") (pinfunction "I/O2_6") (pintype "passive"))
    )
    (net (code "58") (name "Net-(D3-A)") (class "Default")
      (node (ref "D3") (pin "1") (pinfunction "A_1") (pintype "passive"))
      (node (ref "R3") (pin "1") (pinfunction "1_1") (pintype "passive"))
    )
    (net (code "59") (name "Net-(D3-K)") (class "Default")
      (node (ref "D3") (pin "2") (pinfunction "K_2") (pintype "passive"))
      (node (ref "K3") (pin "6") (pinfunction "I/O2_6") (pintype "passive"))
    )
    (net (code "60") (name "Net-(D4-K)") (class "Default")
      (node (ref "C2") (pin "1") (pinfunction "1_1") (pintype "passive"))
      (node (ref "C4") (pin "1") (pinfunction "1_1") (pintype "passive"))
      (node (ref "D4") (pin "2") (pinfunction "K_2") (pintype "passive"))
      (node (ref "U1") (pin "3") (pinfunction "Vin_3") (pintype "passive"))
    )
    (net (code "61") (name "Net-(D5-A)") (class "Default")
      (node (ref "D5") (pin "1") (pinfunction "A_1") (pintype "passive"))
      (node (ref "R14") (pin "1") (pinfunction "1_1") (pintype "passive"))
    )
    (net (code "62") (name "Net-(D5-K)") (class "Default")
      (node (ref "D5") (pin "2") (pinfunction "K_2") (pintype "passive"))
      (node (ref "K4") (pin "6") (pinfunction "I/O2_6") (pintype "passive"))
    )
    (net (code "63") (name "Net-(D6-A)") (class "Default")
      (node (ref "D6") (pin "1") (pinfunction "A_1") (pintype "passive"))
      (node (ref "R15") (pin "1") (pinfunction "1_1") (pintype "passive"))
    )
    (net (code "64") (name "Net-(D6-K)") (class "Default")
      (node (ref "D6") (pin "2") (pinfunction "K_2") (pintype "passive"))
      (node (ref "K5") (pin "6") (pinfunction "I/O2_6") (pintype "passive"))
    )
    (net (code "65") (name "Net-(D7-A)") (class "Default")
      (node (ref "D7") (pin "1") (pinfunction "A_1") (pintype "passive"))
      (node (ref "R16") (pin "1") (pinfunction "1_1") (pintype "passive"))
    )
    (net (code "66") (name "Net-(D7-K)") (class "Default")
      (node (ref "D7") (pin "2") (pinfunction "K_2") (pintype "passive"))
      (node (ref "K6") (pin "6") (pinfunction "I/O2_6") (pintype "passive"))
    )
    (net (code "67") (name "Net-(D8-A)") (class "Default")
      (node (ref "D8") (pin "1") (pinfunction "A_1") (pintype "passive"))
      (node (ref "R13") (pin "2") (pinfunction "2_2") (pintype "passive"))
    )
    (net (code "68") (name "Net-(D9-K)") (class "Default")
      (node (ref "D9") (pin "2") (pinfunction "K_2") (pintype "passive"))
      (node (ref "R33") (pin "2") (pinfunction "2_2") (pintype "passive"))
    )
    (net (code "69") (name "Net-(D10-A)") (class "Default")
      (node (ref "D10") (pin "1") (pinfunction "A_1") (pintype "passive"))
      (node (ref "R35") (pin "1") (pinfunction "1_1") (pintype "passive"))
    )
    (net (code "70") (name "Net-(K1-I{slash}O1-Pad3)") (class "Default")
      (node (ref "K1") (pin "3") (pinfunction "I/O1_3") (pintype "passive"))
      (node (ref "R6") (pin "1") (pinfunction "1_1") (pintype "passive"))
    )
    (net (code "71") (name "Net-(K2-I{slash}O1-Pad3)") (class "Default")
      (node (ref "K2") (pin "3") (pinfunction "I/O1_3") (pintype "passive"))
      (node (ref "R7") (pin "1") (pinfunction "1_1") (pintype "passive"))
    )
    (net (code "72") (name "Net-(K3-I{slash}O1-Pad3)") (class "Default")
      (node (ref "K3") (pin "3") (pinfunction "I/O1_3") (pintype "passive"))
      (node (ref "R8") (pin "1") (pinfunction "1_1") (pintype "passive"))
    )
    (net (code "73") (name "Net-(K4-I{slash}O1-Pad3)") (class "Default")
      (node (ref "K4") (pin "3") (pinfunction "I/O1_3") (pintype "passive"))
      (node (ref "R17") (pin "1") (pinfunction "1_1") (pintype "passive"))
    )
    (net (code "74") (name "Net-(K5-I{slash}O1-Pad3)") (class "Default")
      (node (ref "K5") (pin "3") (pinfunction "I/O1_3") (pintype "passive"))
      (node (ref "R18") (pin "1") (pinfunction "1_1") (pintype "passive"))
    )
    (net (code "75") (name "Net-(K6-I{slash}O1-Pad3)") (class "Default")
      (node (ref "K6") (pin "3") (pinfunction "I/O1_3") (pintype "passive"))
      (node (ref "R19") (pin "1") (pinfunction "1_1") (pintype "passive"))
    )
    (net (code "76") (name "Net-(Q1-G)") (class "Default")
      (node (ref "Q1") (pin "1") (pinfunction "G_1") (pintype "passive"))
      (node (ref "Q3") (pin "3") (pinfunction "C_3") (pintype "passive"))
      (node (ref "R9") (pin "1") (pinfunction "1_1") (pintype "passive"))
    )
    (net (code "77") (name "Net-(Q2-G)") (class "Default")
      (node (ref "Q2") (pin "1") (pinfunction "G_1") (pintype "passive"))
      (node (ref "Q4") (pin "3") (pinfunction "C_3") (pintype "passive"))
      (node (ref "R10") (pin "1") (pinfunction "1_1") (pintype "passive"))
    )
    (net (code "78") (name "Net-(Q3-B)") (class "Default")
      (node (ref "Q3") (pin "1") (pinfunction "B_1") (pintype "passive"))
      (node (ref "R11") (pin "2") (pinfunction "2_2") (pintype "passive"))
    )
    (net (code "79") (name "Net-(Q4-B)") (class "Default")
      (node (ref "Q4") (pin "1") (pinfunction "B_1") (pintype "passive"))
      (node (ref "R12") (pin "2") (pinfunction "2_2") (pintype "passive"))
    )
    (net (code "80") (name "Net-(Q5-G)") (class "Default")
      (node (ref "Q5") (pin "1") (pinfunction "G_1") (pintype "passive"))
      (node (ref "Q6") (pin "3") (pinfunction "C_3") (pintype "passive"))
      (node (ref "R21") (pin "1") (pinfunction "1_1") (pintype "passive"))
    )
    (net (code "81") (name "Net-(Q6-B)") (class "Default")
      (node (ref "Q6") (pin "1") (pinfunction "B_1") (pintype "passive"))
      (node (ref "R22") (pin "2") (pinfunction "2_2") (pintype "passive"))
    )
    (net (code "82") (name "Net-(Q7-G)") (class "Default")
      (node (ref "Q7") (pin "1") (pinfunction "G_1") (pintype "passive"))
      (node (ref "Q9") (pin "3") (pinfunction "C_3") (pintype "passive"))
      (node (ref "R29") (pin "1") (pinfunction "1_1") (pintype "passive"))
    )
    (net (code "83") (name "Net-(Q9-B)") (class "Default")
      (node (ref "Q9") (pin "1") (pinfunction "B_1") (pintype "passive"))
      (node (ref "R31") (pin "2") (pinfunction "2_2") (pintype "passive"))
    )
    (net (code "84") (name "Net-(Q10-B)") (class "Default")
      (node (ref "Q10") (pin "1") (pinfunction "B_1") (pintype "passive"))
      (node (ref "R32") (pin "2") (pinfunction "2_2") (pintype "passive"))
    )
    (net (code "85") (name "Net-(Q10-C)") (class "Default")
      (node (ref "Q10") (pin "3") (pinfunction "C_3") (pintype "passive"))
      (node (ref "Q8") (pin "1") (pinfunction "G_1") (pintype "passive"))
      (node (ref "R30") (pin "1") (pinfunction "1_1") (pintype "passive"))
    )
    (net (code "86") (name "Net-(Q11-B)") (class "Default")
      (node (ref "Q11") (pin "1") (pinfunction "B_1") (pintype "passive"))
      (node (ref "Q13") (pin "3") (pinfunction "C_3") (pintype "passive"))
      (node (ref "R36") (pin "1") (pinfunction "1_1") (pintype "passive"))
    )
    (net (code "87") (name "Net-(Q12-D)") (class "Default")
      (node (ref "Q12") (pin "3") (pinfunction "D_3") (pintype "passive"))
      (node (ref "R34") (pin "1") (pinfunction "1_1") (pintype "passive"))
      (node (ref "R35") (pin "2") (pinfunction "2_2") (pintype "passive"))
    )
    (net (code "88") (name "Net-(Q13-B)") (class "Default")
      (node (ref "Q13") (pin "1") (pinfunction "B_1") (pintype "passive"))
      (node (ref "R38") (pin "1") (pinfunction "1_1") (pintype "passive"))
      (node (ref "R40") (pin "2") (pinfunction "2_2") (pintype "passive"))
    )
    (net (code "89") (name "Net-(Q14-G)") (class "Default")
      (node (ref "Q14") (pin "1") (pinfunction "G_1") (pintype "passive"))
      (node (ref "Q15") (pin "3") (pinfunction "C_3") (pintype "passive"))
      (node (ref "R41") (pin "1") (pinfunction "1_1") (pintype "passive"))
    )
    (net (code "90") (name "Net-(Q15-B)") (class "Default")
      (node (ref "Q15") (pin "1") (pinfunction "B_1") (pintype "passive"))
      (node (ref "R42") (pin "2") (pinfunction "2_2") (pintype "passive"))
    )
    (net (code "91") (name "Net-(Q16-G)") (class "Default")
      (node (ref "Q16") (pin "1") (pinfunction "G_1") (pintype "passive"))
      (node (ref "Q17") (pin "3") (pinfunction "C_3") (pintype "passive"))
      (node (ref "R46") (pin "1") (pinfunction "1_1") (pintype "passive"))
    )
    (net (code "92") (name "Net-(Q17-B)") (class "Default")
      (node (ref "Q17") (pin "1") (pinfunction "B_1") (pintype "passive"))
      (node (ref "R47") (pin "2") (pinfunction "2_2") (pintype "passive"))
    )
    (net (code "93") (name "Net-(Q18-G)") (class "Default")
      (node (ref "Q18") (pin "1") (pinfunction "G_1") (pintype "passive"))
      (node (ref "Q22") (pin "3") (pinfunction "C_3") (pintype "passive"))
      (node (ref "R55") (pin "1") (pinfunction "1_1") (pintype "passive"))
    )
    (net (code "94") (name "Net-(Q19-G)") (class "Default")
      (node (ref "Q19") (pin "1") (pinfunction "G_1") (pintype "passive"))
      (node (ref "Q23") (pin "3") (pinfunction "C_3") (pintype "passive"))
      (node (ref "R56") (pin "1") (pinfunction "1_1") (pintype "passive"))
    )
    (net (code "95") (name "Net-(Q22-B)") (class "Default")
      (node (ref "Q22") (pin "1") (pinfunction "B_1") (pintype "passive"))
      (node (ref "R58") (pin "2") (pinfunction "2_2") (pintype "passive"))
    )
    (net (code "96") (name "Net-(Q23-B)") (class "Default")
      (node (ref "Q23") (pin "1") (pinfunction "B_1") (pintype "passive"))
      (node (ref "R59") (pin "2") (pinfunction "2_2") (pintype "passive"))
    )
    (net (code "97") (name "Net-(U2-VBUS)") (class "Default")
      (node (ref "F1") (pin "1") (pinfunction "1_1") (pintype "passive"))
      (node (ref "U2") (pin "1") (pinfunction "VBUS_1") (pintype "power_in"))
    )
    (net (code "98") (name "Net-(U3-OSC_IN{slash}PD0)") (class "Default")
      (node (ref "C5") (pin "2") (pinfunction "2_2") (pintype "passive"))
      (node (ref "U3") (pin "5") (pinfunction "OSC_IN/PD0_5") (pintype "input"))
      (node (ref "Y1") (pin "2") (pinfunction "OSC2_2") (pintype "passive"))
    )
    (net (code "99") (name "Net-(U3-OSC_OUT{slash}PD1)") (class "Default")
      (node (ref "C6") (pin "2") (pinfunction "2_2") (pintype "passive"))
      (node (ref "U3") (pin "6") (pinfunction "OSC_OUT/PD1_6") (pintype "output"))
      (node (ref "Y1") (pin "1") (pinfunction "OSC1_1") (pintype "passive"))
    )
    (net (code "100") (name "Net-(U4-S)") (class "Default")
      (node (ref "R52") (pin "2") (pinfunction "2_2") (pintype "passive"))
      (node (ref "U4") (pin "8") (pinfunction "S_8") (pintype "passive"))
    )
    (net (code "101") (name "VCC3.3") (class "Default")
      (node (ref "C1") (pin "1") (pinfunction "1_1") (pintype "passive"))
      (node (ref "C11") (pin "2") (pinfunction "2_2") (pintype "passive"))
      (node (ref "C12") (pin "2") (pinfunction "2_2") (pintype "passive"))
      (node (ref "C13") (pin "2") (pinfunction "2_2") (pintype "passive"))
      (node (ref "C14") (pin "2") (pinfunction "2_2") (pintype "passive"))
      (node (ref "C3") (pin "1") (pinfunction "1_1") (pintype "passive"))
      (node (ref "JP1") (pin "1") (pinfunction "1_1") (pintype "passive"))
      (node (ref "Q12") (pin "1") (pinfunction "G_1") (pintype "passive"))
      (node (ref "R1") (pin "2") (pinfunction "2_2") (pintype "passive"))
      (node (ref "R14") (pin "2") (pinfunction "2_2") (pintype "passive"))
      (node (ref "R15") (pin "2") (pinfunction "2_2") (pintype "passive"))
      (node (ref "R16") (pin "2") (pinfunction "2_2") (pintype "passive"))
      (node (ref "R17") (pin "2") (pinfunction "2_2") (pintype "passive"))
      (node (ref "R18") (pin "2") (pinfunction "2_2") (pintype "passive"))
      (node (ref "R19") (pin "2") (pinfunction "2_2") (pintype "passive"))
      (node (ref "R2") (pin "2") (pinfunction "2_2") (pintype "passive"))
      (node (ref "R23") (pin "2") (pinfunction "2_2") (pintype "passive"))
      (node (ref "R27") (pin "2") (pinfunction "2_2") (pintype "passive"))
      (node (ref "R3") (pin "2") (pinfunction "2_2") (pintype "passive"))
      (node (ref "R37") (pin "2") (pinfunction "2_2") (pintype "passive"))
      (node (ref "R6") (pin "2") (pinfunction "2_2") (pintype "passive"))
      (node (ref "R7") (pin "2") (pinfunction "2_2") (pintype "passive"))
      (node (ref "R8") (pin "2") (pinfunction "2_2") (pintype "passive"))
      (node (ref "SMBJ2") (pin "2") (pinfunction "K_2") (pintype "passive"))
      (node (ref "U1") (pin "2") (pinfunction "Vout_2") (pintype "passive"))
      (node (ref "U1") (pin "4") (pinfunction "Vout_4") (pintype "passive"))
      (node (ref "U3") (pin "1") (pinfunction "VBAT_1") (pintype "power_in"))
      (node (ref "U3") (pin "13") (pinfunction "VDDA_13") (pintype "power_in"))
      (node (ref "U3") (pin "19") (pinfunction "VDD_4_19") (pintype "power_in"))
      (node (ref "U3") (pin "32") (pinfunction "VDD_1_32") (pintype "power_in"))
      (node (ref "U3") (pin "48") (pinfunction "VDD_2_48") (pintype "power_in"))
      (node (ref "U3") (pin "64") (pinfunction "VDD_3_64") (pintype "power_in"))
      (node (ref "U4") (pin "5") (pinfunction "Vref_5") (pintype "passive"))
    )
    (net (code "102") (name "VCC5") (class "Default")
      (node (ref "C18") (pin "2") (pinfunction "2_2") (pintype "passive"))
      (node (ref "D4") (pin "1") (pinfunction "A_1") (pintype "passive"))
      (node (ref "D9") (pin "1") (pinfunction "A_1") (pintype "passive"))
      (node (ref "F1") (pin "2") (pinfunction "2_2") (pintype "passive"))
      (node (ref "P1") (pin "1") (pinfunction "1_1") (pintype "passive"))
      (node (ref "P2") (pin "1") (pinfunction "1_1") (pintype "passive"))
      (node (ref "P3") (pin "1") (pinfunction "1_1") (pintype "passive"))
      (node (ref "P4") (pin "1") (pinfunction "1_1") (pintype "passive"))
      (node (ref "P5") (pin "1") (pinfunction "1_1") (pintype "passive"))
      (node (ref "P6") (pin "1") (pinfunction "1_1") (pintype "passive"))
      (node (ref "P7") (pin "1") (pinfunction "1_1") (pintype "passive"))
      (node (ref "R10") (pin "2") (pinfunction "2_2") (pintype "passive"))
      (node (ref "R13") (pin "1") (pinfunction "1_1") (pintype "passive"))
      (node (ref "R20") (pin "2") (pinfunction "2_2") (pintype "passive"))
      (node (ref "R21") (pin "2") (pinfunction "2_2") (pintype "passive"))
      (node (ref "R25") (pin "2") (pinfunction "2_2") (pintype "passive"))
      (node (ref "R26") (pin "2") (pinfunction "2_2") (pintype "passive"))
      (node (ref "R29") (pin "2") (pinfunction "2_2") (pintype "passive"))
      (node (ref "R30") (pin "2") (pinfunction "2_2") (pintype "passive"))
      (node (ref "R34") (pin "2") (pinfunction "2_2") (pintype "passive"))
      (node (ref "R36") (pin "2") (pinfunction "2_2") (pintype "passive"))
      (node (ref "R39") (pin "2") (pinfunction "2_2") (pintype "passive"))
      (node (ref "R4") (pin "2") (pinfunction "2_2") (pintype "passive"))
      (node (ref "R41") (pin "2") (pinfunction "2_2") (pintype "passive"))
      (node (ref "R43") (pin "2") (pinfunction "2_2") (pintype "passive"))
      (node (ref "R46") (pin "2") (pinfunction "2_2") (pintype "passive"))
      (node (ref "R5") (pin "2") (pinfunction "2_2") (pintype "passive"))
      (node (ref "R50") (pin "2") (pinfunction "2_2") (pintype "passive"))
      (node (ref "R51") (pin "2") (pinfunction "2_2") (pintype "passive"))
      (node (ref "R55") (pin "2") (pinfunction "2_2") (pintype "passive"))
      (node (ref "R56") (pin "2") (pinfunction "2_2") (pintype "passive"))
      (node (ref "R9") (pin "2") (pinfunction "2_2") (pintype "passive"))
      (node (ref "SMBJ1") (pin "2") (pinfunction "K_2") (pintype "passive"))
      (node (ref "U4") (pin "3") (pinfunction "VCC_3") (pintype "passive"))
    )
    (net (code "103") (name "unconnected-(D11-N-Pad3)") (class "Default")
      (node (ref "D11") (pin "3") (pinfunction "N_3") (pintype "passive"))
    )
    (net (code "104") (name "unconnected-(D12-N-Pad3)") (class "Default")
      (node (ref "D12") (pin "3") (pinfunction "N_3") (pintype "passive"))
    )
    (net (code "105") (name "unconnected-(K1-I{slash}O1-Pad1)") (class "Default")
      (node (ref "K1") (pin "1") (pinfunction "I/O1_1") (pintype "passive"))
    )
    (net (code "106") (name "unconnected-(K1-I{slash}O2-Pad4)") (class "Default")
      (node (ref "K1") (pin "4") (pinfunction "I/O2_4") (pintype "passive"))
    )
    (net (code "107") (name "unconnected-(K2-I{slash}O1-Pad1)") (class "Default")
      (node (ref "K2") (pin "1") (pinfunction "I/O1_1") (pintype "passive"))
    )
    (net (code "108") (name "unconnected-(K2-I{slash}O2-Pad4)") (class "Default")
      (node (ref "K2") (pin "4") (pinfunction "I/O2_4") (pintype "passive"))
    )
    (net (code "109") (name "unconnected-(K3-I{slash}O1-Pad1)") (class "Default")
      (node (ref "K3") (pin "1") (pinfunction "I/O1_1") (pintype "passive"))
    )
    (net (code "110") (name "unconnected-(K3-I{slash}O2-Pad4)") (class "Default")
      (node (ref "K3") (pin "4") (pinfunction "I/O2_4") (pintype "passive"))
    )
    (net (code "111") (name "unconnected-(K4-I{slash}O1-Pad1)") (class "Default")
      (node (ref "K4") (pin "1") (pinfunction "I/O1_1") (pintype "passive"))
    )
    (net (code "112") (name "unconnected-(K4-I{slash}O2-Pad4)") (class "Default")
      (node (ref "K4") (pin "4") (pinfunction "I/O2_4") (pintype "passive"))
    )
    (net (code "113") (name "unconnected-(K5-I{slash}O1-Pad1)") (class "Default")
      (node (ref "K5") (pin "1") (pinfunction "I/O1_1") (pintype "passive"))
    )
    (net (code "114") (name "unconnected-(K5-I{slash}O2-Pad4)") (class "Default")
      (node (ref "K5") (pin "4") (pinfunction "I/O2_4") (pintype "passive"))
    )
    (net (code "115") (name "unconnected-(K6-I{slash}O1-Pad1)") (class "Default")
      (node (ref "K6") (pin "1") (pinfunction "I/O1_1") (pintype "passive"))
    )
    (net (code "116") (name "unconnected-(K6-I{slash}O2-Pad4)") (class "Default")
      (node (ref "K6") (pin "4") (pinfunction "I/O2_4") (pintype "passive"))
    )
    (net (code "117") (name "unconnected-(U2-D+-Pad3)") (class "Default")
      (node (ref "U2") (pin "3") (pinfunction "D+_3") (pintype "bidirectional"))
    )
    (net (code "118") (name "unconnected-(U2-D--Pad2)") (class "Default")
      (node (ref "U2") (pin "2") (pinfunction "D-_2") (pintype "bidirectional"))
    )
    (net (code "119") (name "unconnected-(U2-ID-Pad4)") (class "Default")
      (node (ref "U2") (pin "4") (pinfunction "ID_4") (pintype "bidirectional+no_connect"))
    )
    (net (code "120") (name "unconnected-(U3-PA0-WKUP-Pad14)") (class "Default")
      (node (ref "U3") (pin "14") (pinfunction "PA0-WKUP_14") (pintype "bidirectional"))
    )
    (net (code "121") (name "unconnected-(U3-PA3-Pad17)") (class "Default")
      (node (ref "U3") (pin "17") (pinfunction "PA3_17") (pintype "bidirectional"))
    )
    (net (code "122") (name "unconnected-(U3-PA8-Pad41)") (class "Default")
      (node (ref "U3") (pin "41") (pinfunction "PA8_41") (pintype "bidirectional"))
    )
    (net (code "123") (name "unconnected-(U3-PB6-Pad58)") (class "Default")
      (node (ref "U3") (pin "58") (pinfunction "PB6_58") (pintype "bidirectional"))
    )
    (net (code "124") (name "unconnected-(U3-PB7-Pad59)") (class "Default")
      (node (ref "U3") (pin "59") (pinfunction "PB7_59") (pintype "bidirectional"))
    )
    (net (code "125") (name "unconnected-(U3-PB15-Pad36)") (class "Default")
      (node (ref "U3") (pin "36") (pinfunction "PB15_36") (pintype "bidirectional"))
    )
    (net (code "126") (name "unconnected-(U3-PC0-Pad8)") (class "Default")
      (node (ref "U3") (pin "8") (pinfunction "PC0_8") (pintype "bidirectional"))
    )
    (net (code "127") (name "unconnected-(U3-PC1-Pad9)") (class "Default")
      (node (ref "U3") (pin "9") (pinfunction "PC1_9") (pintype "bidirectional"))
    )
    (net (code "128") (name "unconnected-(U3-PC2-Pad10)") (class "Default")
      (node (ref "U3") (pin "10") (pinfunction "PC2_10") (pintype "bidirectional"))
    )
    (net (code "129") (name "unconnected-(U3-PC3-Pad11)") (class "Default")
      (node (ref "U3") (pin "11") (pinfunction "PC3_11") (pintype "bidirectional"))
    )
    (net (code "130") (name "unconnected-(U3-PC6-Pad37)") (class "Default")
      (node (ref "U3") (pin "37") (pinfunction "PC6_37") (pintype "bidirectional"))
    )
    (net (code "131") (name "unconnected-(U3-PC7-Pad38)") (class "Default")
      (node (ref "U3") (pin "38") (pinfunction "PC7_38") (pintype "bidirectional"))
    )
    (net (code "132") (name "unconnected-(U3-PC8-Pad39)") (class "Default")
      (node (ref "U3") (pin "39") (pinfunction "PC8_39") (pintype "bidirectional"))
    )
    (net (code "133") (name "unconnected-(U3-PC9-Pad40)") (class "Default")
      (node (ref "U3") (pin "40") (pinfunction "PC9_40") (pintype "bidirectional"))
    )
    (net (code "134") (name "unconnected-(U3-PC14-OSC32_IN-Pad3)") (class "Default")
      (node (ref "U3") (pin "3") (pinfunction "PC14-OSC32_IN_3") (pintype "bidirectional"))
    )
    (net (code "135") (name "unconnected-(U3-PC15-OSC32_OUT-Pad4)") (class "Default")
      (node (ref "U3") (pin "4") (pinfunction "PC15-OSC32_OUT_4") (pintype "bidirectional"))
    )
  )
)
